# circle_button.net
KiCad netlist of a schematic drawn in EAGLE
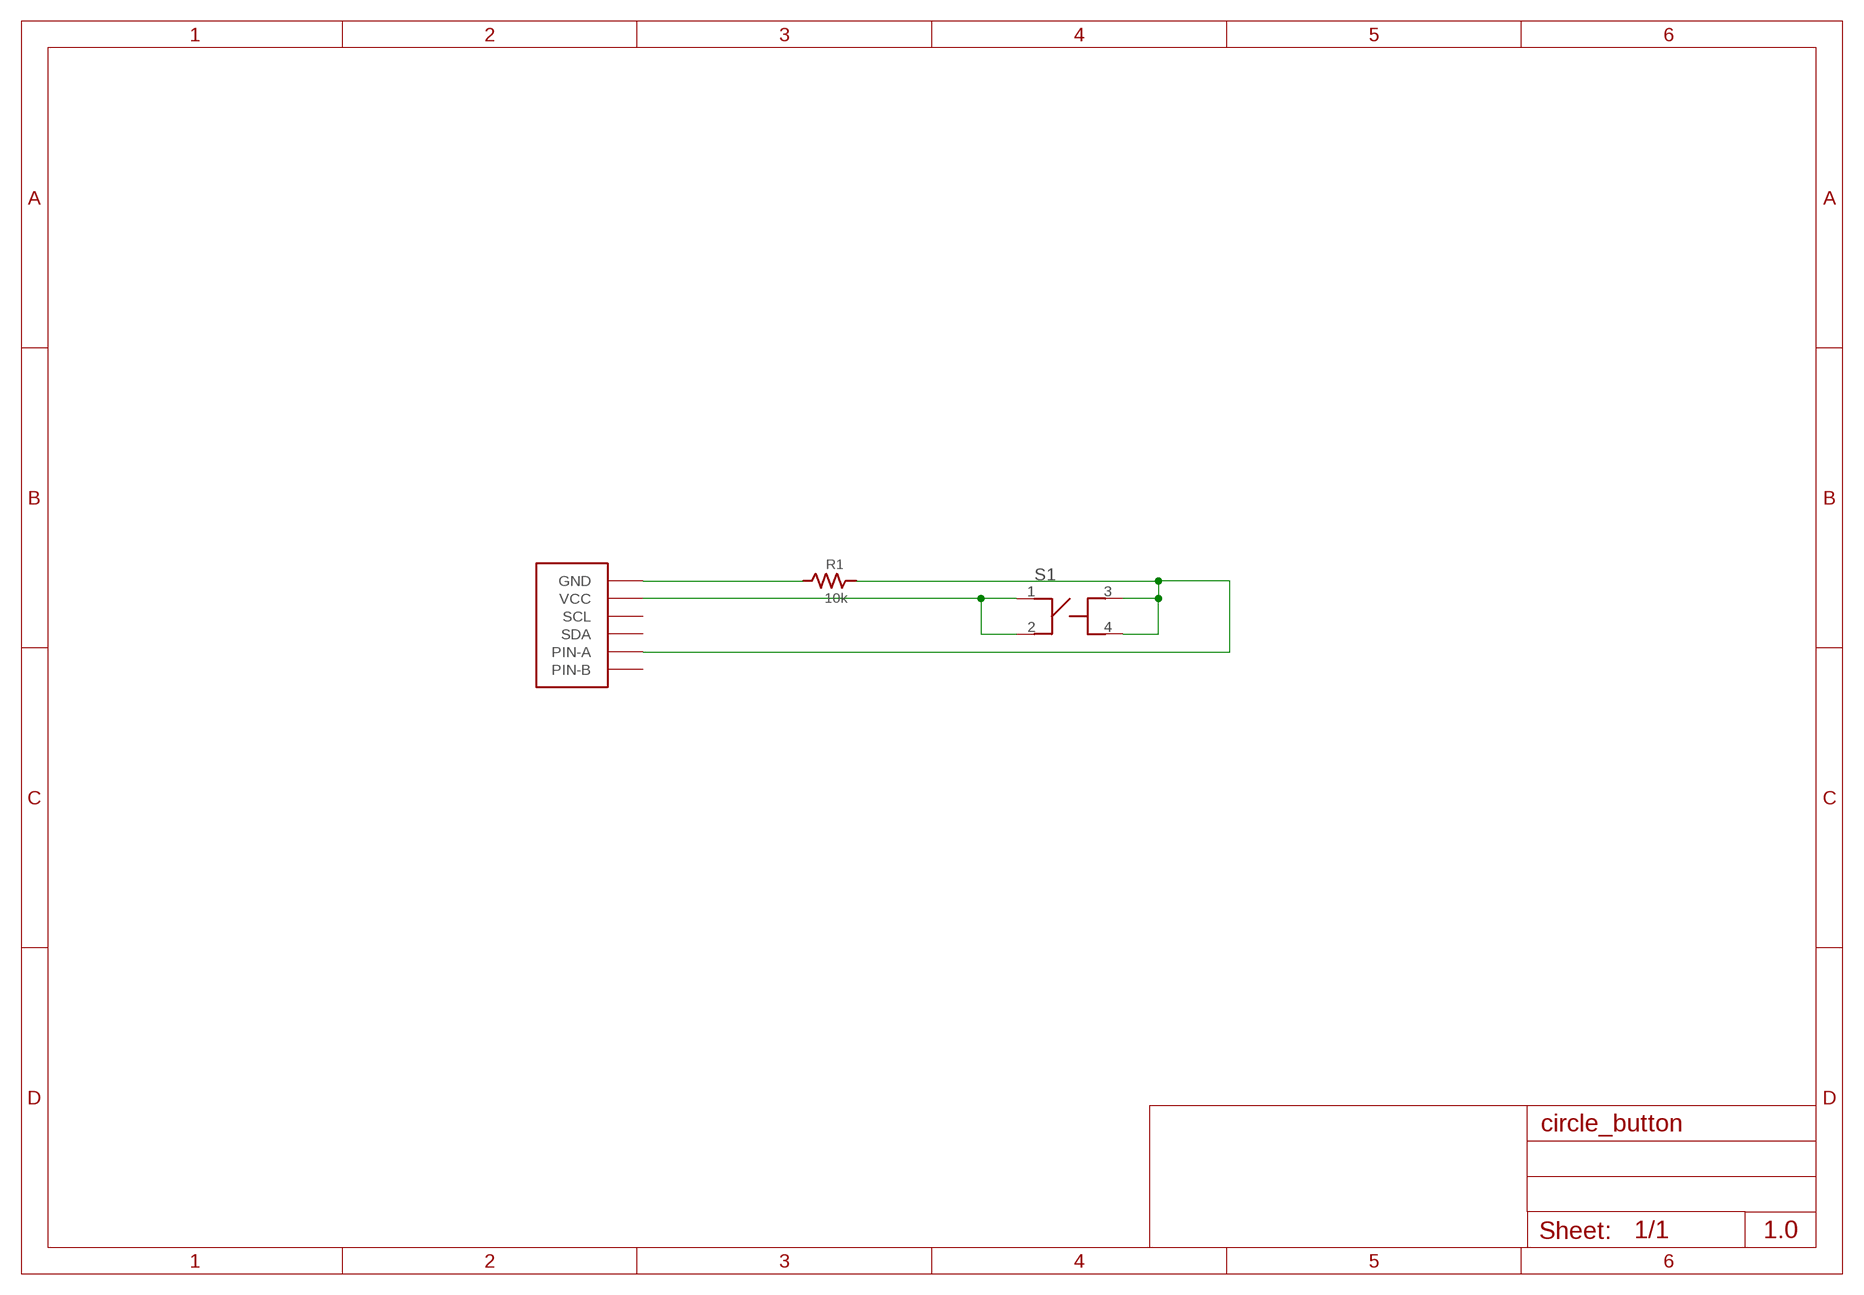
[diagram p0: schematic, sheet 1]

(export (version "E")
  (design (tool "Eeschema 10.0.6"))
  (components
    (comp (ref "R1")
      (value "10k")
      (footprint "eagle-import:0402")
      (libsource (lib "eagle-import") (part "RESISTOR-0402"))
    )
    (comp (ref "S1")
      (value "SWITCH-LS6J2M-T")
      (footprint "eagle-import:SWITCH-LS6J2M-T")
      (libsource (lib "eagle-import") (part "SWITCH-LS6J2M-T"))
    )
    (comp (ref "U$2")
      (value "FABO-NANO")
      (footprint "eagle-import:FABO-NANO")
      (libsource (lib "eagle-import") (part "FABO-NANO"))
    )
  )
  (nets
    (net (code "1") (name "Net-(R1-1)") (class "Default")
      (node (ref "R1") (pin "P$1") (pinfunction "1_P$1") (pintype "bidirectional"))
      (node (ref "U$2") (pin "GND") (pinfunction "GND_GND") (pintype "bidirectional"))
    )
    (net (code "2") (name "Net-(R1-2)") (class "Default")
      (node (ref "R1") (pin "P$2") (pinfunction "2_P$2") (pintype "bidirectional"))
      (node (ref "S1") (pin "3") (pinfunction "3_3") (pintype "bidirectional"))
      (node (ref "S1") (pin "4") (pinfunction "4_4") (pintype "bidirectional"))
      (node (ref "U$2") (pin "2") (pinfunction "PIN-A_2") (pintype "bidirectional"))
    )
    (net (code "3") (name "Net-(S1-Pad1)") (class "Default")
      (node (ref "S1") (pin "1") (pinfunction "1_1") (pintype "bidirectional"))
      (node (ref "S1") (pin "2") (pinfunction "2_2") (pintype "bidirectional"))
      (node (ref "U$2") (pin "VCC") (pinfunction "VCC_VCC") (pintype "bidirectional"))
    )
    (net (code "4") (name "unconnected-(U$2-PIN-B-Pad3)") (class "Default")
      (node (ref "U$2") (pin "3") (pinfunction "PIN-B_3") (pintype "bidirectional"))
    )
    (net (code "5") (name "unconnected-(U$2-SCL-Pad0)") (class "Default")
      (node (ref "U$2") (pin "0") (pinfunction "SCL_0") (pintype "bidirectional"))
    )
    (net (code "6") (name "unconnected-(U$2-SDA-Pad1)") (class "Default")
      (node (ref "U$2") (pin "1") (pinfunction "SDA_1") (pintype "bidirectional"))
    )
  )
)
